# prva_shema.net
KiCad netlist of a schematic drawn in EAGLE
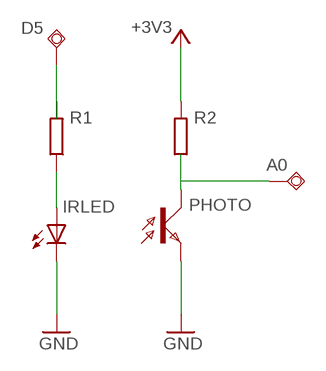
[diagram p0: schematic, sheet 1]

(export (version "E")
  (design (tool "Eeschema 10.0.6"))
  (components
    (comp (ref "A0")
      (value "TPSQB1,27")
      (footprint "eagle-import:B1,27")
      (libsource (lib "eagle-import") (part "TPSQB1,27"))
    )
    (comp (ref "D5")
      (value "TPSQB1,27")
      (footprint "eagle-import:B1,27")
      (libsource (lib "eagle-import") (part "TPSQB1,27"))
    )
    (comp (ref "IRLED")
      (value "SFH482")
      (footprint "eagle-import:SFH482")
      (libsource (lib "eagle-import") (part "SFH482"))
    )
    (comp (ref "PHOTO")
      (value "BPX81")
      (footprint "eagle-import:BPX81")
      (libsource (lib "eagle-import") (part "BPX81"))
    )
    (comp (ref "R1")
      (value "R-EU_0204/5")
      (footprint "eagle-import:0204_5")
      (libsource (lib "eagle-import") (part "R-EU_0204/5"))
    )
    (comp (ref "R2")
      (value "R-EU_0204/5")
      (footprint "eagle-import:0204_5")
      (libsource (lib "eagle-import") (part "R-EU_0204/5"))
    )
  )
  (nets
    (net (code "1") (name "+3V3") (class "Default")
      (node (ref "R2") (pin "2") (pinfunction "2_2") (pintype "passive"))
    )
    (net (code "2") (name "GND") (class "Default")
      (node (ref "IRLED") (pin "K") (pinfunction "C_K") (pintype "passive"))
      (node (ref "PHOTO") (pin "E") (pinfunction "E_E") (pintype "passive"))
    )
    (net (code "3") (name "Net-(A0-PadTP)") (class "Default")
      (node (ref "A0") (pin "TP") (pinfunction "TP_TP") (pintype "input"))
      (node (ref "PHOTO") (pin "C") (pinfunction "C_C") (pintype "passive"))
      (node (ref "R2") (pin "1") (pinfunction "1_1") (pintype "passive"))
    )
    (net (code "4") (name "Net-(D5-PadTP)") (class "Default")
      (node (ref "D5") (pin "TP") (pinfunction "TP_TP") (pintype "input"))
      (node (ref "R1") (pin "2") (pinfunction "2_2") (pintype "passive"))
    )
    (net (code "5") (name "Net-(IRLED-PadA)") (class "Default")
      (node (ref "IRLED") (pin "A") (pinfunction "A_A") (pintype "passive"))
      (node (ref "R1") (pin "1") (pinfunction "1_1") (pintype "passive"))
    )
  )
)
